# Sheet2.net
KiCad netlist of a schematic drawn in Altium Designer
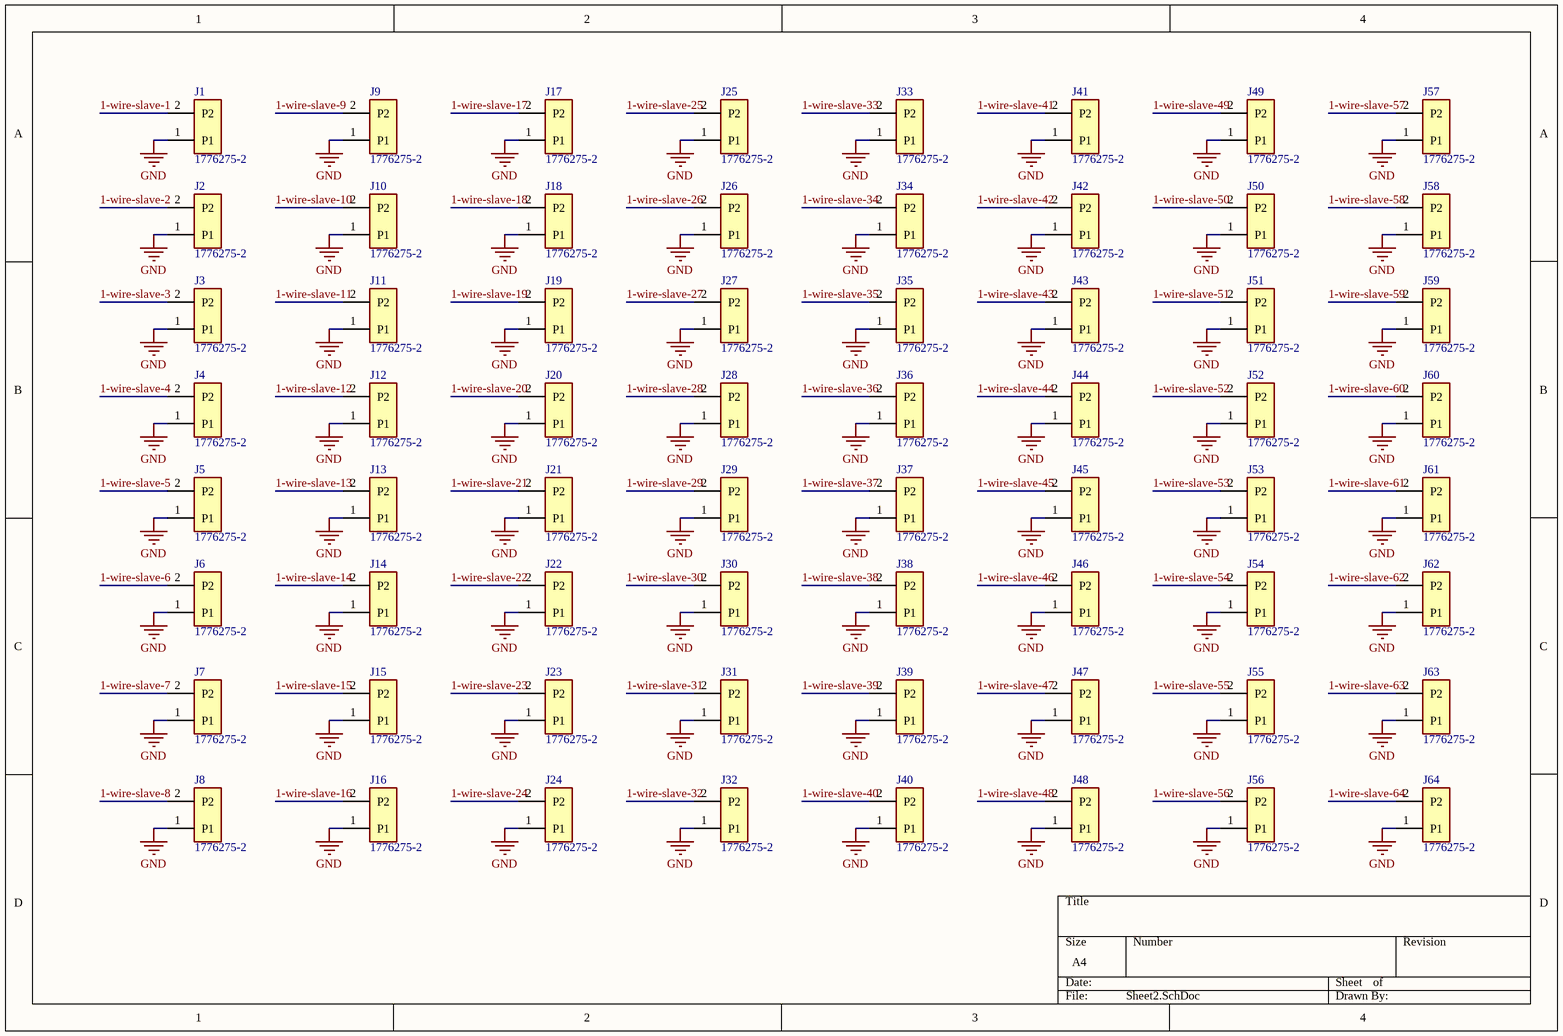
[diagram p0: Sheet2.SchDoc]

(export (version "E")
  (design (tool "Eeschema 10.0.6"))
  (components
    (comp (ref "J1")
      (value "1776275-2")
      (footprint "1776275-2:TE_1776275-2")
      (description "TERM BLOCK 2POS SIDE ENT 3.5MM")
      (fields (field (name "MF") "{'manufacturer': u'TE Connectivity'}"))
      (libsource (lib "1776275-2") (part "1776275-2"))
    )
    (comp (ref "J2")
      (value "1776275-2")
      (footprint "1776275-2:TE_1776275-2")
      (description "TERM BLOCK 2POS SIDE ENT 3.5MM")
      (fields (field (name "MF") "{'manufacturer': u'TE Connectivity'}"))
      (libsource (lib "1776275-2") (part "1776275-2"))
    )
    (comp (ref "J3")
      (value "1776275-2")
      (footprint "1776275-2:TE_1776275-2")
      (description "TERM BLOCK 2POS SIDE ENT 3.5MM")
      (fields (field (name "MF") "{'manufacturer': u'TE Connectivity'}"))
      (libsource (lib "1776275-2") (part "1776275-2"))
    )
    (comp (ref "J4")
      (value "1776275-2")
      (footprint "1776275-2:TE_1776275-2")
      (description "TERM BLOCK 2POS SIDE ENT 3.5MM")
      (fields (field (name "MF") "{'manufacturer': u'TE Connectivity'}"))
      (libsource (lib "1776275-2") (part "1776275-2"))
    )
    (comp (ref "J5")
      (value "1776275-2")
      (footprint "1776275-2:TE_1776275-2")
      (description "TERM BLOCK 2POS SIDE ENT 3.5MM")
      (fields (field (name "MF") "{'manufacturer': u'TE Connectivity'}"))
      (libsource (lib "1776275-2") (part "1776275-2"))
    )
    (comp (ref "J6")
      (value "1776275-2")
      (footprint "1776275-2:TE_1776275-2")
      (description "TERM BLOCK 2POS SIDE ENT 3.5MM")
      (fields (field (name "MF") "{'manufacturer': u'TE Connectivity'}"))
      (libsource (lib "1776275-2") (part "1776275-2"))
    )
    (comp (ref "J7")
      (value "1776275-2")
      (footprint "1776275-2:TE_1776275-2")
      (description "TERM BLOCK 2POS SIDE ENT 3.5MM")
      (fields (field (name "MF") "{'manufacturer': u'TE Connectivity'}"))
      (libsource (lib "1776275-2") (part "1776275-2"))
    )
    (comp (ref "J8")
      (value "1776275-2")
      (footprint "1776275-2:TE_1776275-2")
      (description "TERM BLOCK 2POS SIDE ENT 3.5MM")
      (fields (field (name "MF") "{'manufacturer': u'TE Connectivity'}"))
      (libsource (lib "1776275-2") (part "1776275-2"))
    )
    (comp (ref "J9")
      (value "1776275-2")
      (footprint "1776275-2:TE_1776275-2")
      (description "TERM BLOCK 2POS SIDE ENT 3.5MM")
      (fields (field (name "MF") "{'manufacturer': u'TE Connectivity'}"))
      (libsource (lib "1776275-2") (part "1776275-2"))
    )
    (comp (ref "J10")
      (value "1776275-2")
      (footprint "1776275-2:TE_1776275-2")
      (description "TERM BLOCK 2POS SIDE ENT 3.5MM")
      (fields (field (name "MF") "{'manufacturer': u'TE Connectivity'}"))
      (libsource (lib "1776275-2") (part "1776275-2"))
    )
    (comp (ref "J11")
      (value "1776275-2")
      (footprint "1776275-2:TE_1776275-2")
      (description "TERM BLOCK 2POS SIDE ENT 3.5MM")
      (fields (field (name "MF") "{'manufacturer': u'TE Connectivity'}"))
      (libsource (lib "1776275-2") (part "1776275-2"))
    )
    (comp (ref "J12")
      (value "1776275-2")
      (footprint "1776275-2:TE_1776275-2")
      (description "TERM BLOCK 2POS SIDE ENT 3.5MM")
      (fields (field (name "MF") "{'manufacturer': u'TE Connectivity'}"))
      (libsource (lib "1776275-2") (part "1776275-2"))
    )
    (comp (ref "J13")
      (value "1776275-2")
      (footprint "1776275-2:TE_1776275-2")
      (description "TERM BLOCK 2POS SIDE ENT 3.5MM")
      (fields (field (name "MF") "{'manufacturer': u'TE Connectivity'}"))
      (libsource (lib "1776275-2") (part "1776275-2"))
    )
    (comp (ref "J14")
      (value "1776275-2")
      (footprint "1776275-2:TE_1776275-2")
      (description "TERM BLOCK 2POS SIDE ENT 3.5MM")
      (fields (field (name "MF") "{'manufacturer': u'TE Connectivity'}"))
      (libsource (lib "1776275-2") (part "1776275-2"))
    )
    (comp (ref "J15")
      (value "1776275-2")
      (footprint "1776275-2:TE_1776275-2")
      (description "TERM BLOCK 2POS SIDE ENT 3.5MM")
      (fields (field (name "MF") "{'manufacturer': u'TE Connectivity'}"))
      (libsource (lib "1776275-2") (part "1776275-2"))
    )
    (comp (ref "J16")
      (value "1776275-2")
      (footprint "1776275-2:TE_1776275-2")
      (description "TERM BLOCK 2POS SIDE ENT 3.5MM")
      (fields (field (name "MF") "{'manufacturer': u'TE Connectivity'}"))
      (libsource (lib "1776275-2") (part "1776275-2"))
    )
    (comp (ref "J17")
      (value "1776275-2")
      (footprint "1776275-2:TE_1776275-2")
      (description "TERM BLOCK 2POS SIDE ENT 3.5MM")
      (fields (field (name "MF") "{'manufacturer': u'TE Connectivity'}"))
      (libsource (lib "1776275-2") (part "1776275-2"))
    )
    (comp (ref "J18")
      (value "1776275-2")
      (footprint "1776275-2:TE_1776275-2")
      (description "TERM BLOCK 2POS SIDE ENT 3.5MM")
      (fields (field (name "MF") "{'manufacturer': u'TE Connectivity'}"))
      (libsource (lib "1776275-2") (part "1776275-2"))
    )
    (comp (ref "J19")
      (value "1776275-2")
      (footprint "1776275-2:TE_1776275-2")
      (description "TERM BLOCK 2POS SIDE ENT 3.5MM")
      (fields (field (name "MF") "{'manufacturer': u'TE Connectivity'}"))
      (libsource (lib "1776275-2") (part "1776275-2"))
    )
    (comp (ref "J20")
      (value "1776275-2")
      (footprint "1776275-2:TE_1776275-2")
      (description "TERM BLOCK 2POS SIDE ENT 3.5MM")
      (fields (field (name "MF") "{'manufacturer': u'TE Connectivity'}"))
      (libsource (lib "1776275-2") (part "1776275-2"))
    )
    (comp (ref "J21")
      (value "1776275-2")
      (footprint "1776275-2:TE_1776275-2")
      (description "TERM BLOCK 2POS SIDE ENT 3.5MM")
      (fields (field (name "MF") "{'manufacturer': u'TE Connectivity'}"))
      (libsource (lib "1776275-2") (part "1776275-2"))
    )
    (comp (ref "J22")
      (value "1776275-2")
      (footprint "1776275-2:TE_1776275-2")
      (description "TERM BLOCK 2POS SIDE ENT 3.5MM")
      (fields (field (name "MF") "{'manufacturer': u'TE Connectivity'}"))
      (libsource (lib "1776275-2") (part "1776275-2"))
    )
    (comp (ref "J23")
      (value "1776275-2")
      (footprint "1776275-2:TE_1776275-2")
      (description "TERM BLOCK 2POS SIDE ENT 3.5MM")
      (fields (field (name "MF") "{'manufacturer': u'TE Connectivity'}"))
      (libsource (lib "1776275-2") (part "1776275-2"))
    )
    (comp (ref "J24")
      (value "1776275-2")
      (footprint "1776275-2:TE_1776275-2")
      (description "TERM BLOCK 2POS SIDE ENT 3.5MM")
      (fields (field (name "MF") "{'manufacturer': u'TE Connectivity'}"))
      (libsource (lib "1776275-2") (part "1776275-2"))
    )
    (comp (ref "J25")
      (value "1776275-2")
      (footprint "1776275-2:TE_1776275-2")
      (description "TERM BLOCK 2POS SIDE ENT 3.5MM")
      (fields (field (name "MF") "{'manufacturer': u'TE Connectivity'}"))
      (libsource (lib "1776275-2") (part "1776275-2"))
    )
    (comp (ref "J26")
      (value "1776275-2")
      (footprint "1776275-2:TE_1776275-2")
      (description "TERM BLOCK 2POS SIDE ENT 3.5MM")
      (fields (field (name "MF") "{'manufacturer': u'TE Connectivity'}"))
      (libsource (lib "1776275-2") (part "1776275-2"))
    )
    (comp (ref "J27")
      (value "1776275-2")
      (footprint "1776275-2:TE_1776275-2")
      (description "TERM BLOCK 2POS SIDE ENT 3.5MM")
      (fields (field (name "MF") "{'manufacturer': u'TE Connectivity'}"))
      (libsource (lib "1776275-2") (part "1776275-2"))
    )
    (comp (ref "J28")
      (value "1776275-2")
      (footprint "1776275-2:TE_1776275-2")
      (description "TERM BLOCK 2POS SIDE ENT 3.5MM")
      (fields (field (name "MF") "{'manufacturer': u'TE Connectivity'}"))
      (libsource (lib "1776275-2") (part "1776275-2"))
    )
    (comp (ref "J29")
      (value "1776275-2")
      (footprint "1776275-2:TE_1776275-2")
      (description "TERM BLOCK 2POS SIDE ENT 3.5MM")
      (fields (field (name "MF") "{'manufacturer': u'TE Connectivity'}"))
      (libsource (lib "1776275-2") (part "1776275-2"))
    )
    (comp (ref "J30")
      (value "1776275-2")
      (footprint "1776275-2:TE_1776275-2")
      (description "TERM BLOCK 2POS SIDE ENT 3.5MM")
      (fields (field (name "MF") "{'manufacturer': u'TE Connectivity'}"))
      (libsource (lib "1776275-2") (part "1776275-2"))
    )
    (comp (ref "J31")
      (value "1776275-2")
      (footprint "1776275-2:TE_1776275-2")
      (description "TERM BLOCK 2POS SIDE ENT 3.5MM")
      (fields (field (name "MF") "{'manufacturer': u'TE Connectivity'}"))
      (libsource (lib "1776275-2") (part "1776275-2"))
    )
    (comp (ref "J32")
      (value "1776275-2")
      (footprint "1776275-2:TE_1776275-2")
      (description "TERM BLOCK 2POS SIDE ENT 3.5MM")
      (fields (field (name "MF") "{'manufacturer': u'TE Connectivity'}"))
      (libsource (lib "1776275-2") (part "1776275-2"))
    )
    (comp (ref "J33")
      (value "1776275-2")
      (footprint "1776275-2:TE_1776275-2")
      (description "TERM BLOCK 2POS SIDE ENT 3.5MM")
      (fields (field (name "MF") "{'manufacturer': u'TE Connectivity'}"))
      (libsource (lib "1776275-2") (part "1776275-2"))
    )
    (comp (ref "J34")
      (value "1776275-2")
      (footprint "1776275-2:TE_1776275-2")
      (description "TERM BLOCK 2POS SIDE ENT 3.5MM")
      (fields (field (name "MF") "{'manufacturer': u'TE Connectivity'}"))
      (libsource (lib "1776275-2") (part "1776275-2"))
    )
    (comp (ref "J35")
      (value "1776275-2")
      (footprint "1776275-2:TE_1776275-2")
      (description "TERM BLOCK 2POS SIDE ENT 3.5MM")
      (fields (field (name "MF") "{'manufacturer': u'TE Connectivity'}"))
      (libsource (lib "1776275-2") (part "1776275-2"))
    )
    (comp (ref "J36")
      (value "1776275-2")
      (footprint "1776275-2:TE_1776275-2")
      (description "TERM BLOCK 2POS SIDE ENT 3.5MM")
      (fields (field (name "MF") "{'manufacturer': u'TE Connectivity'}"))
      (libsource (lib "1776275-2") (part "1776275-2"))
    )
    (comp (ref "J37")
      (value "1776275-2")
      (footprint "1776275-2:TE_1776275-2")
      (description "TERM BLOCK 2POS SIDE ENT 3.5MM")
      (fields (field (name "MF") "{'manufacturer': u'TE Connectivity'}"))
      (libsource (lib "1776275-2") (part "1776275-2"))
    )
    (comp (ref "J38")
      (value "1776275-2")
      (footprint "1776275-2:TE_1776275-2")
      (description "TERM BLOCK 2POS SIDE ENT 3.5MM")
      (fields (field (name "MF") "{'manufacturer': u'TE Connectivity'}"))
      (libsource (lib "1776275-2") (part "1776275-2"))
    )
    (comp (ref "J39")
      (value "1776275-2")
      (footprint "1776275-2:TE_1776275-2")
      (description "TERM BLOCK 2POS SIDE ENT 3.5MM")
      (fields (field (name "MF") "{'manufacturer': u'TE Connectivity'}"))
      (libsource (lib "1776275-2") (part "1776275-2"))
    )
    (comp (ref "J40")
      (value "1776275-2")
      (footprint "1776275-2:TE_1776275-2")
      (description "TERM BLOCK 2POS SIDE ENT 3.5MM")
      (fields (field (name "MF") "{'manufacturer': u'TE Connectivity'}"))
      (libsource (lib "1776275-2") (part "1776275-2"))
    )
    (comp (ref "J41")
      (value "1776275-2")
      (footprint "1776275-2:TE_1776275-2")
      (description "TERM BLOCK 2POS SIDE ENT 3.5MM")
      (fields (field (name "MF") "{'manufacturer': u'TE Connectivity'}"))
      (libsource (lib "1776275-2") (part "1776275-2"))
    )
    (comp (ref "J42")
      (value "1776275-2")
      (footprint "1776275-2:TE_1776275-2")
      (description "TERM BLOCK 2POS SIDE ENT 3.5MM")
      (fields (field (name "MF") "{'manufacturer': u'TE Connectivity'}"))
      (libsource (lib "1776275-2") (part "1776275-2"))
    )
    (comp (ref "J43")
      (value "1776275-2")
      (footprint "1776275-2:TE_1776275-2")
      (description "TERM BLOCK 2POS SIDE ENT 3.5MM")
      (fields (field (name "MF") "{'manufacturer': u'TE Connectivity'}"))
      (libsource (lib "1776275-2") (part "1776275-2"))
    )
    (comp (ref "J44")
      (value "1776275-2")
      (footprint "1776275-2:TE_1776275-2")
      (description "TERM BLOCK 2POS SIDE ENT 3.5MM")
      (fields (field (name "MF") "{'manufacturer': u'TE Connectivity'}"))
      (libsource (lib "1776275-2") (part "1776275-2"))
    )
    (comp (ref "J45")
      (value "1776275-2")
      (footprint "1776275-2:TE_1776275-2")
      (description "TERM BLOCK 2POS SIDE ENT 3.5MM")
      (fields (field (name "MF") "{'manufacturer': u'TE Connectivity'}"))
      (libsource (lib "1776275-2") (part "1776275-2"))
    )
    (comp (ref "J46")
      (value "1776275-2")
      (footprint "1776275-2:TE_1776275-2")
      (description "TERM BLOCK 2POS SIDE ENT 3.5MM")
      (fields (field (name "MF") "{'manufacturer': u'TE Connectivity'}"))
      (libsource (lib "1776275-2") (part "1776275-2"))
    )
    (comp (ref "J47")
      (value "1776275-2")
      (footprint "1776275-2:TE_1776275-2")
      (description "TERM BLOCK 2POS SIDE ENT 3.5MM")
      (fields (field (name "MF") "{'manufacturer': u'TE Connectivity'}"))
      (libsource (lib "1776275-2") (part "1776275-2"))
    )
    (comp (ref "J48")
      (value "1776275-2")
      (footprint "1776275-2:TE_1776275-2")
      (description "TERM BLOCK 2POS SIDE ENT 3.5MM")
      (fields (field (name "MF") "{'manufacturer': u'TE Connectivity'}"))
      (libsource (lib "1776275-2") (part "1776275-2"))
    )
    (comp (ref "J49")
      (value "1776275-2")
      (footprint "1776275-2:TE_1776275-2")
      (description "TERM BLOCK 2POS SIDE ENT 3.5MM")
      (fields (field (name "MF") "{'manufacturer': u'TE Connectivity'}"))
      (libsource (lib "1776275-2") (part "1776275-2"))
    )
    (comp (ref "J50")
      (value "1776275-2")
      (footprint "1776275-2:TE_1776275-2")
      (description "TERM BLOCK 2POS SIDE ENT 3.5MM")
      (fields (field (name "MF") "{'manufacturer': u'TE Connectivity'}"))
      (libsource (lib "1776275-2") (part "1776275-2"))
    )
    (comp (ref "J51")
      (value "1776275-2")
      (footprint "1776275-2:TE_1776275-2")
      (description "TERM BLOCK 2POS SIDE ENT 3.5MM")
      (fields (field (name "MF") "{'manufacturer': u'TE Connectivity'}"))
      (libsource (lib "1776275-2") (part "1776275-2"))
    )
    (comp (ref "J52")
      (value "1776275-2")
      (footprint "1776275-2:TE_1776275-2")
      (description "TERM BLOCK 2POS SIDE ENT 3.5MM")
      (fields (field (name "MF") "{'manufacturer': u'TE Connectivity'}"))
      (libsource (lib "1776275-2") (part "1776275-2"))
    )
    (comp (ref "J53")
      (value "1776275-2")
      (footprint "1776275-2:TE_1776275-2")
      (description "TERM BLOCK 2POS SIDE ENT 3.5MM")
      (fields (field (name "MF") "{'manufacturer': u'TE Connectivity'}"))
      (libsource (lib "1776275-2") (part "1776275-2"))
    )
    (comp (ref "J54")
      (value "1776275-2")
      (footprint "1776275-2:TE_1776275-2")
      (description "TERM BLOCK 2POS SIDE ENT 3.5MM")
      (fields (field (name "MF") "{'manufacturer': u'TE Connectivity'}"))
      (libsource (lib "1776275-2") (part "1776275-2"))
    )
    (comp (ref "J55")
      (value "1776275-2")
      (footprint "1776275-2:TE_1776275-2")
      (description "TERM BLOCK 2POS SIDE ENT 3.5MM")
      (fields (field (name "MF") "{'manufacturer': u'TE Connectivity'}"))
      (libsource (lib "1776275-2") (part "1776275-2"))
    )
    (comp (ref "J56")
      (value "1776275-2")
      (footprint "1776275-2:TE_1776275-2")
      (description "TERM BLOCK 2POS SIDE ENT 3.5MM")
      (fields (field (name "MF") "{'manufacturer': u'TE Connectivity'}"))
      (libsource (lib "1776275-2") (part "1776275-2"))
    )
    (comp (ref "J57")
      (value "1776275-2")
      (footprint "1776275-2:TE_1776275-2")
      (description "TERM BLOCK 2POS SIDE ENT 3.5MM")
      (fields (field (name "MF") "{'manufacturer': u'TE Connectivity'}"))
      (libsource (lib "1776275-2") (part "1776275-2"))
    )
    (comp (ref "J58")
      (value "1776275-2")
      (footprint "1776275-2:TE_1776275-2")
      (description "TERM BLOCK 2POS SIDE ENT 3.5MM")
      (fields (field (name "MF") "{'manufacturer': u'TE Connectivity'}"))
      (libsource (lib "1776275-2") (part "1776275-2"))
    )
    (comp (ref "J59")
      (value "1776275-2")
      (footprint "1776275-2:TE_1776275-2")
      (description "TERM BLOCK 2POS SIDE ENT 3.5MM")
      (fields (field (name "MF") "{'manufacturer': u'TE Connectivity'}"))
      (libsource (lib "1776275-2") (part "1776275-2"))
    )
    (comp (ref "J60")
      (value "1776275-2")
      (footprint "1776275-2:TE_1776275-2")
      (description "TERM BLOCK 2POS SIDE ENT 3.5MM")
      (fields (field (name "MF") "{'manufacturer': u'TE Connectivity'}"))
      (libsource (lib "1776275-2") (part "1776275-2"))
    )
    (comp (ref "J61")
      (value "1776275-2")
      (footprint "1776275-2:TE_1776275-2")
      (description "TERM BLOCK 2POS SIDE ENT 3.5MM")
      (fields (field (name "MF") "{'manufacturer': u'TE Connectivity'}"))
      (libsource (lib "1776275-2") (part "1776275-2"))
    )
    (comp (ref "J62")
      (value "1776275-2")
      (footprint "1776275-2:TE_1776275-2")
      (description "TERM BLOCK 2POS SIDE ENT 3.5MM")
      (fields (field (name "MF") "{'manufacturer': u'TE Connectivity'}"))
      (libsource (lib "1776275-2") (part "1776275-2"))
    )
    (comp (ref "J63")
      (value "1776275-2")
      (footprint "1776275-2:TE_1776275-2")
      (description "TERM BLOCK 2POS SIDE ENT 3.5MM")
      (fields (field (name "MF") "{'manufacturer': u'TE Connectivity'}"))
      (libsource (lib "1776275-2") (part "1776275-2"))
    )
    (comp (ref "J64")
      (value "1776275-2")
      (footprint "1776275-2:TE_1776275-2")
      (description "TERM BLOCK 2POS SIDE ENT 3.5MM")
      (fields (field (name "MF") "{'manufacturer': u'TE Connectivity'}"))
      (libsource (lib "1776275-2") (part "1776275-2"))
    )
  )
  (nets
    (net (code "1") (name "/1-wire-slave-1") (class "Default")
      (node (ref "J1") (pin "2") (pinfunction "P2_2") (pintype "passive"))
    )
    (net (code "2") (name "/1-wire-slave-2") (class "Default")
      (node (ref "J2") (pin "2") (pinfunction "P2_2") (pintype "passive"))
    )
    (net (code "3") (name "/1-wire-slave-3") (class "Default")
      (node (ref "J3") (pin "2") (pinfunction "P2_2") (pintype "passive"))
    )
    (net (code "4") (name "/1-wire-slave-4") (class "Default")
      (node (ref "J4") (pin "2") (pinfunction "P2_2") (pintype "passive"))
    )
    (net (code "5") (name "/1-wire-slave-5") (class "Default")
      (node (ref "J5") (pin "2") (pinfunction "P2_2") (pintype "passive"))
    )
    (net (code "6") (name "/1-wire-slave-6") (class "Default")
      (node (ref "J6") (pin "2") (pinfunction "P2_2") (pintype "passive"))
    )
    (net (code "7") (name "/1-wire-slave-7") (class "Default")
      (node (ref "J7") (pin "2") (pinfunction "P2_2") (pintype "passive"))
    )
    (net (code "8") (name "/1-wire-slave-8") (class "Default")
      (node (ref "J8") (pin "2") (pinfunction "P2_2") (pintype "passive"))
    )
    (net (code "9") (name "/1-wire-slave-9") (class "Default")
      (node (ref "J9") (pin "2") (pinfunction "P2_2") (pintype "passive"))
    )
    (net (code "10") (name "/1-wire-slave-10") (class "Default")
      (node (ref "J10") (pin "2") (pinfunction "P2_2") (pintype "passive"))
    )
    (net (code "11") (name "/1-wire-slave-11") (class "Default")
      (node (ref "J11") (pin "2") (pinfunction "P2_2") (pintype "passive"))
    )
    (net (code "12") (name "/1-wire-slave-12") (class "Default")
      (node (ref "J12") (pin "2") (pinfunction "P2_2") (pintype "passive"))
    )
    (net (code "13") (name "/1-wire-slave-13") (class "Default")
      (node (ref "J13") (pin "2") (pinfunction "P2_2") (pintype "passive"))
    )
    (net (code "14") (name "/1-wire-slave-14") (class "Default")
      (node (ref "J14") (pin "2") (pinfunction "P2_2") (pintype "passive"))
    )
    (net (code "15") (name "/1-wire-slave-15") (class "Default")
      (node (ref "J15") (pin "2") (pinfunction "P2_2") (pintype "passive"))
    )
    (net (code "16") (name "/1-wire-slave-16") (class "Default")
      (node (ref "J16") (pin "2") (pinfunction "P2_2") (pintype "passive"))
    )
    (net (code "17") (name "/1-wire-slave-17") (class "Default")
      (node (ref "J17") (pin "2") (pinfunction "P2_2") (pintype "passive"))
    )
    (net (code "18") (name "/1-wire-slave-18") (class "Default")
      (node (ref "J18") (pin "2") (pinfunction "P2_2") (pintype "passive"))
    )
    (net (code "19") (name "/1-wire-slave-19") (class "Default")
      (node (ref "J19") (pin "2") (pinfunction "P2_2") (pintype "passive"))
    )
    (net (code "20") (name "/1-wire-slave-20") (class "Default")
      (node (ref "J20") (pin "2") (pinfunction "P2_2") (pintype "passive"))
    )
    (net (code "21") (name "/1-wire-slave-21") (class "Default")
      (node (ref "J21") (pin "2") (pinfunction "P2_2") (pintype "passive"))
    )
    (net (code "22") (name "/1-wire-slave-22") (class "Default")
      (node (ref "J22") (pin "2") (pinfunction "P2_2") (pintype "passive"))
    )
    (net (code "23") (name "/1-wire-slave-23") (class "Default")
      (node (ref "J23") (pin "2") (pinfunction "P2_2") (pintype "passive"))
    )
    (net (code "24") (name "/1-wire-slave-24") (class "Default")
      (node (ref "J24") (pin "2") (pinfunction "P2_2") (pintype "passive"))
    )
    (net (code "25") (name "/1-wire-slave-25") (class "Default")
      (node (ref "J25") (pin "2") (pinfunction "P2_2") (pintype "passive"))
    )
    (net (code "26") (name "/1-wire-slave-26") (class "Default")
      (node (ref "J26") (pin "2") (pinfunction "P2_2") (pintype "passive"))
    )
    (net (code "27") (name "/1-wire-slave-27") (class "Default")
      (node (ref "J27") (pin "2") (pinfunction "P2_2") (pintype "passive"))
    )
    (net (code "28") (name "/1-wire-slave-28") (class "Default")
      (node (ref "J28") (pin "2") (pinfunction "P2_2") (pintype "passive"))
    )
    (net (code "29") (name "/1-wire-slave-29") (class "Default")
      (node (ref "J29") (pin "2") (pinfunction "P2_2") (pintype "passive"))
    )
    (net (code "30") (name "/1-wire-slave-30") (class "Default")
      (node (ref "J30") (pin "2") (pinfunction "P2_2") (pintype "passive"))
    )
    (net (code "31") (name "/1-wire-slave-31") (class "Default")
      (node (ref "J31") (pin "2") (pinfunction "P2_2") (pintype "passive"))
    )
    (net (code "32") (name "/1-wire-slave-32") (class "Default")
      (node (ref "J32") (pin "2") (pinfunction "P2_2") (pintype "passive"))
    )
    (net (code "33") (name "/1-wire-slave-33") (class "Default")
      (node (ref "J33") (pin "2") (pinfunction "P2_2") (pintype "passive"))
    )
    (net (code "34") (name "/1-wire-slave-34") (class "Default")
      (node (ref "J34") (pin "2") (pinfunction "P2_2") (pintype "passive"))
    )
    (net (code "35") (name "/1-wire-slave-35") (class "Default")
      (node (ref "J35") (pin "2") (pinfunction "P2_2") (pintype "passive"))
    )
    (net (code "36") (name "/1-wire-slave-36") (class "Default")
      (node (ref "J36") (pin "2") (pinfunction "P2_2") (pintype "passive"))
    )
    (net (code "37") (name "/1-wire-slave-37") (class "Default")
      (node (ref "J37") (pin "2") (pinfunction "P2_2") (pintype "passive"))
    )
    (net (code "38") (name "/1-wire-slave-38") (class "Default")
      (node (ref "J38") (pin "2") (pinfunction "P2_2") (pintype "passive"))
    )
    (net (code "39") (name "/1-wire-slave-39") (class "Default")
      (node (ref "J39") (pin "2") (pinfunction "P2_2") (pintype "passive"))
    )
    (net (code "40") (name "/1-wire-slave-40") (class "Default")
      (node (ref "J40") (pin "2") (pinfunction "P2_2") (pintype "passive"))
    )
    (net (code "41") (name "/1-wire-slave-41") (class "Default")
      (node (ref "J41") (pin "2") (pinfunction "P2_2") (pintype "passive"))
    )
    (net (code "42") (name "/1-wire-slave-42") (class "Default")
      (node (ref "J42") (pin "2") (pinfunction "P2_2") (pintype "passive"))
    )
    (net (code "43") (name "/1-wire-slave-43") (class "Default")
      (node (ref "J43") (pin "2") (pinfunction "P2_2") (pintype "passive"))
    )
    (net (code "44") (name "/1-wire-slave-44") (class "Default")
      (node (ref "J44") (pin "2") (pinfunction "P2_2") (pintype "passive"))
    )
    (net (code "45") (name "/1-wire-slave-45") (class "Default")
      (node (ref "J45") (pin "2") (pinfunction "P2_2") (pintype "passive"))
    )
    (net (code "46") (name "/1-wire-slave-46") (class "Default")
      (node (ref "J46") (pin "2") (pinfunction "P2_2") (pintype "passive"))
    )
    (net (code "47") (name "/1-wire-slave-47") (class "Default")
      (node (ref "J47") (pin "2") (pinfunction "P2_2") (pintype "passive"))
    )
    (net (code "48") (name "/1-wire-slave-48") (class "Default")
      (node (ref "J48") (pin "2") (pinfunction "P2_2") (pintype "passive"))
    )
    (net (code "49") (name "/1-wire-slave-49") (class "Default")
      (node (ref "J49") (pin "2") (pinfunction "P2_2") (pintype "passive"))
    )
    (net (code "50") (name "/1-wire-slave-50") (class "Default")
      (node (ref "J50") (pin "2") (pinfunction "P2_2") (pintype "passive"))
    )
    (net (code "51") (name "/1-wire-slave-51") (class "Default")
      (node (ref "J51") (pin "2") (pinfunction "P2_2") (pintype "passive"))
    )
    (net (code "52") (name "/1-wire-slave-52") (class "Default")
      (node (ref "J52") (pin "2") (pinfunction "P2_2") (pintype "passive"))
    )
    (net (code "53") (name "/1-wire-slave-53") (class "Default")
      (node (ref "J53") (pin "2") (pinfunction "P2_2") (pintype "passive"))
    )
    (net (code "54") (name "/1-wire-slave-54") (class "Default")
      (node (ref "J54") (pin "2") (pinfunction "P2_2") (pintype "passive"))
    )
    (net (code "55") (name "/1-wire-slave-55") (class "Default")
      (node (ref "J55") (pin "2") (pinfunction "P2_2") (pintype "passive"))
    )
    (net (code "56") (name "/1-wire-slave-56") (class "Default")
      (node (ref "J56") (pin "2") (pinfunction "P2_2") (pintype "passive"))
    )
    (net (code "57") (name "/1-wire-slave-57") (class "Default")
      (node (ref "J57") (pin "2") (pinfunction "P2_2") (pintype "passive"))
    )
    (net (code "58") (name "/1-wire-slave-58") (class "Default")
      (node (ref "J58") (pin "2") (pinfunction "P2_2") (pintype "passive"))
    )
    (net (code "59") (name "/1-wire-slave-59") (class "Default")
      (node (ref "J59") (pin "2") (pinfunction "P2_2") (pintype "passive"))
    )
    (net (code "60") (name "/1-wire-slave-60") (class "Default")
      (node (ref "J60") (pin "2") (pinfunction "P2_2") (pintype "passive"))
    )
    (net (code "61") (name "/1-wire-slave-61") (class "Default")
      (node (ref "J61") (pin "2") (pinfunction "P2_2") (pintype "passive"))
    )
    (net (code "62") (name "/1-wire-slave-62") (class "Default")
      (node (ref "J62") (pin "2") (pinfunction "P2_2") (pintype "passive"))
    )
    (net (code "63") (name "/1-wire-slave-63") (class "Default")
      (node (ref "J63") (pin "2") (pinfunction "P2_2") (pintype "passive"))
    )
    (net (code "64") (name "/1-wire-slave-64") (class "Default")
      (node (ref "J64") (pin "2") (pinfunction "P2_2") (pintype "passive"))
    )
    (net (code "65") (name "GND") (class "Default")
      (node (ref "J1") (pin "1") (pinfunction "P1_1") (pintype "passive"))
      (node (ref "J10") (pin "1") (pinfunction "P1_1") (pintype "passive"))
      (node (ref "J11") (pin "1") (pinfunction "P1_1") (pintype "passive"))
      (node (ref "J12") (pin "1") (pinfunction "P1_1") (pintype "passive"))
      (node (ref "J13") (pin "1") (pinfunction "P1_1") (pintype "passive"))
      (node (ref "J14") (pin "1") (pinfunction "P1_1") (pintype "passive"))
      (node (ref "J15") (pin "1") (pinfunction "P1_1") (pintype "passive"))
      (node (ref "J16") (pin "1") (pinfunction "P1_1") (pintype "passive"))
      (node (ref "J17") (pin "1") (pinfunction "P1_1") (pintype "passive"))
      (node (ref "J18") (pin "1") (pinfunction "P1_1") (pintype "passive"))
      (node (ref "J19") (pin "1") (pinfunction "P1_1") (pintype "passive"))
      (node (ref "J2") (pin "1") (pinfunction "P1_1") (pintype "passive"))
      (node (ref "J20") (pin "1") (pinfunction "P1_1") (pintype "passive"))
      (node (ref "J21") (pin "1") (pinfunction "P1_1") (pintype "passive"))
      (node (ref "J22") (pin "1") (pinfunction "P1_1") (pintype "passive"))
      (node (ref "J23") (pin "1") (pinfunction "P1_1") (pintype "passive"))
      (node (ref "J24") (pin "1") (pinfunction "P1_1") (pintype "passive"))
      (node (ref "J25") (pin "1") (pinfunction "P1_1") (pintype "passive"))
      (node (ref "J26") (pin "1") (pinfunction "P1_1") (pintype "passive"))
      (node (ref "J27") (pin "1") (pinfunction "P1_1") (pintype "passive"))
      (node (ref "J28") (pin "1") (pinfunction "P1_1") (pintype "passive"))
      (node (ref "J29") (pin "1") (pinfunction "P1_1") (pintype "passive"))
      (node (ref "J3") (pin "1") (pinfunction "P1_1") (pintype "passive"))
      (node (ref "J30") (pin "1") (pinfunction "P1_1") (pintype "passive"))
      (node (ref "J31") (pin "1") (pinfunction "P1_1") (pintype "passive"))
      (node (ref "J32") (pin "1") (pinfunction "P1_1") (pintype "passive"))
      (node (ref "J33") (pin "1") (pinfunction "P1_1") (pintype "passive"))
      (node (ref "J34") (pin "1") (pinfunction "P1_1") (pintype "passive"))
      (node (ref "J35") (pin "1") (pinfunction "P1_1") (pintype "passive"))
      (node (ref "J36") (pin "1") (pinfunction "P1_1") (pintype "passive"))
      (node (ref "J37") (pin "1") (pinfunction "P1_1") (pintype "passive"))
      (node (ref "J38") (pin "1") (pinfunction "P1_1") (pintype "passive"))
      (node (ref "J39") (pin "1") (pinfunction "P1_1") (pintype "passive"))
      (node (ref "J4") (pin "1") (pinfunction "P1_1") (pintype "passive"))
      (node (ref "J40") (pin "1") (pinfunction "P1_1") (pintype "passive"))
      (node (ref "J41") (pin "1") (pinfunction "P1_1") (pintype "passive"))
      (node (ref "J42") (pin "1") (pinfunction "P1_1") (pintype "passive"))
      (node (ref "J43") (pin "1") (pinfunction "P1_1") (pintype "passive"))
      (node (ref "J44") (pin "1") (pinfunction "P1_1") (pintype "passive"))
      (node (ref "J45") (pin "1") (pinfunction "P1_1") (pintype "passive"))
      (node (ref "J46") (pin "1") (pinfunction "P1_1") (pintype "passive"))
      (node (ref "J47") (pin "1") (pinfunction "P1_1") (pintype "passive"))
      (node (ref "J48") (pin "1") (pinfunction "P1_1") (pintype "passive"))
      (node (ref "J49") (pin "1") (pinfunction "P1_1") (pintype "passive"))
      (node (ref "J5") (pin "1") (pinfunction "P1_1") (pintype "passive"))
      (node (ref "J50") (pin "1") (pinfunction "P1_1") (pintype "passive"))
      (node (ref "J51") (pin "1") (pinfunction "P1_1") (pintype "passive"))
      (node (ref "J52") (pin "1") (pinfunction "P1_1") (pintype "passive"))
      (node (ref "J53") (pin "1") (pinfunction "P1_1") (pintype "passive"))
      (node (ref "J54") (pin "1") (pinfunction "P1_1") (pintype "passive"))
      (node (ref "J55") (pin "1") (pinfunction "P1_1") (pintype "passive"))
      (node (ref "J56") (pin "1") (pinfunction "P1_1") (pintype "passive"))
      (node (ref "J57") (pin "1") (pinfunction "P1_1") (pintype "passive"))
      (node (ref "J58") (pin "1") (pinfunction "P1_1") (pintype "passive"))
      (node (ref "J59") (pin "1") (pinfunction "P1_1") (pintype "passive"))
      (node (ref "J6") (pin "1") (pinfunction "P1_1") (pintype "passive"))
      (node (ref "J60") (pin "1") (pinfunction "P1_1") (pintype "passive"))
      (node (ref "J61") (pin "1") (pinfunction "P1_1") (pintype "passive"))
      (node (ref "J62") (pin "1") (pinfunction "P1_1") (pintype "passive"))
      (node (ref "J63") (pin "1") (pinfunction "P1_1") (pintype "passive"))
      (node (ref "J64") (pin "1") (pinfunction "P1_1") (pintype "passive"))
      (node (ref "J7") (pin "1") (pinfunction "P1_1") (pintype "passive"))
      (node (ref "J8") (pin "1") (pinfunction "P1_1") (pintype "passive"))
      (node (ref "J9") (pin "1") (pinfunction "P1_1") (pintype "passive"))
    )
  )
)
